# electrophy_NRF.net
KiCad netlist of a schematic drawn in EAGLE
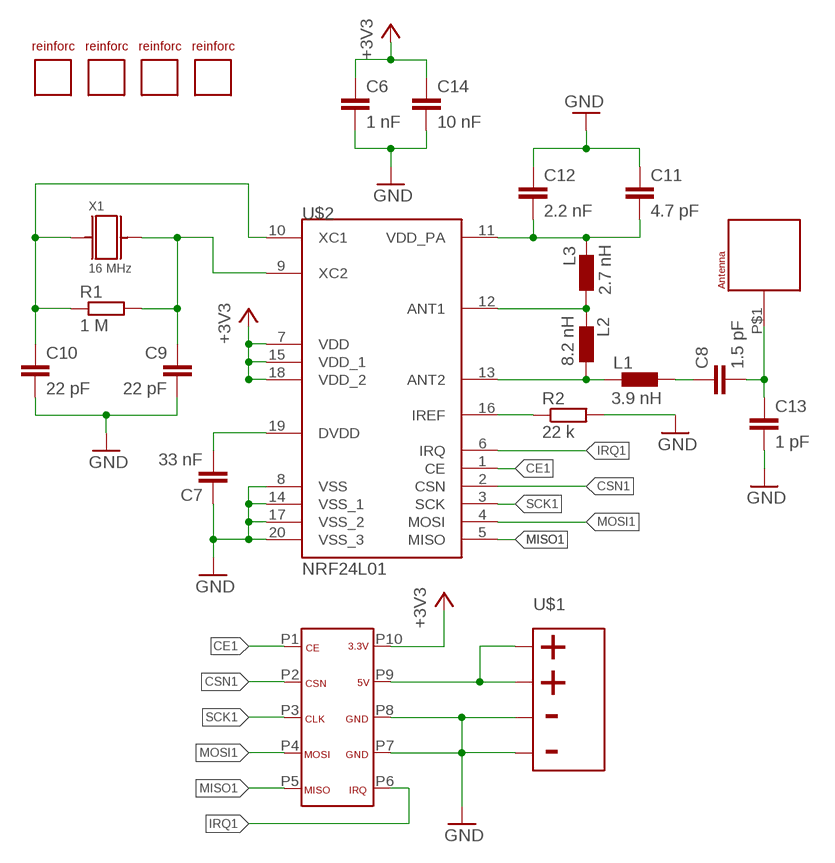
[diagram p0: schematic, sheet 1]

(export (version "E")
  (design (tool "Eeschema 10.0.6"))
  (components
    (comp (ref "C6")
      (value "1 nF")
      (footprint "eagle-import:C0603")
      (libsource (lib "eagle-import") (part "C-EUC0603"))
    )
    (comp (ref "C7")
      (value "33 nF")
      (footprint "eagle-import:C0603")
      (libsource (lib "eagle-import") (part "C-EUC0603"))
    )
    (comp (ref "C8")
      (value "1.5 pF")
      (footprint "eagle-import:C0603")
      (libsource (lib "eagle-import") (part "C-EUC0603"))
    )
    (comp (ref "C9")
      (value "22 pF")
      (footprint "eagle-import:C0603")
      (libsource (lib "eagle-import") (part "C-EUC0603"))
    )
    (comp (ref "C10")
      (value "22 pF")
      (footprint "eagle-import:C0603")
      (libsource (lib "eagle-import") (part "C-EUC0603"))
    )
    (comp (ref "C11")
      (value "4.7 pF")
      (footprint "eagle-import:C0603")
      (libsource (lib "eagle-import") (part "C-EUC0603"))
    )
    (comp (ref "C12")
      (value "2.2 nF")
      (footprint "eagle-import:C0603")
      (libsource (lib "eagle-import") (part "C-EUC0603"))
    )
    (comp (ref "C13")
      (value "1 pF")
      (footprint "eagle-import:C0603")
      (libsource (lib "eagle-import") (part "C-EUC0603"))
    )
    (comp (ref "C14")
      (value "10 nF")
      (footprint "eagle-import:C0603")
      (libsource (lib "eagle-import") (part "C-EUC0603"))
    )
    (comp (ref "L1")
      (value "3.9 nH")
      (footprint "eagle-import:C0603")
      (libsource (lib "eagle-import") (part "INDUCTANCE"))
    )
    (comp (ref "L2")
      (value "8.2 nH")
      (footprint "eagle-import:C0603")
      (libsource (lib "eagle-import") (part "INDUCTANCE"))
    )
    (comp (ref "L3")
      (value "2.7 nH")
      (footprint "eagle-import:C0603")
      (libsource (lib "eagle-import") (part "INDUCTANCE"))
    )
    (comp (ref "R1")
      (value "1 M")
      (footprint "eagle-import:R0603")
      (libsource (lib "eagle-import") (part "R-EU_R0603"))
    )
    (comp (ref "R2")
      (value "22 k")
      (footprint "eagle-import:R0603")
      (libsource (lib "eagle-import") (part "R-EU_R0603"))
    )
    (comp (ref "U$1")
      (value "BAT_HOLDER")
      (footprint "eagle-import:BAT_HOLDER")
      (libsource (lib "eagle-import") (part "BAT_HOLDER"))
    )
    (comp (ref "U$2")
      (value "NRF24L01")
      (footprint "eagle-import:QFN20")
      (libsource (lib "eagle-import") (part "NRF24L01"))
    )
    (comp (ref "U$3")
      (value "WURTH_ANTENNA")
      (footprint "eagle-import:WURTH_ANTENNA")
      (libsource (lib "eagle-import") (part "WURTH_ANTENNA"))
    )
    (comp (ref "U$4")
      (value "DF12-10-MALE")
      (footprint "eagle-import:DF12-10-MALE")
      (libsource (lib "eagle-import") (part "DF12-10-MALE"))
    )
    (comp (ref "U$5")
      (value "REINFORCEMENT")
      (footprint "eagle-import:REINFORCEMENT")
      (libsource (lib "eagle-import") (part "REINFORCEMENT"))
    )
    (comp (ref "U$6")
      (value "REINFORCEMENT")
      (footprint "eagle-import:REINFORCEMENT")
      (libsource (lib "eagle-import") (part "REINFORCEMENT"))
    )
    (comp (ref "U$7")
      (value "REINFORCEMENT")
      (footprint "eagle-import:REINFORCEMENT")
      (libsource (lib "eagle-import") (part "REINFORCEMENT"))
    )
    (comp (ref "U$8")
      (value "REINFORCEMENT")
      (footprint "eagle-import:REINFORCEMENT")
      (libsource (lib "eagle-import") (part "REINFORCEMENT"))
    )
    (comp (ref "X1")
      (value "16 MHz")
      (footprint "eagle-import:NRF_XTAL")
      (libsource (lib "eagle-import") (part "NRF_XTAL"))
    )
  )
  (nets
    (net (code "1") (name "+3V3") (class "Default")
      (node (ref "C14") (pin "1") (pinfunction "1_1") (pintype "passive"))
      (node (ref "C6") (pin "1") (pinfunction "1_1") (pintype "passive"))
      (node (ref "U$2") (pin "15") (pinfunction "VDD_1_15") (pintype "bidirectional"))
      (node (ref "U$2") (pin "18") (pinfunction "VDD_2_18") (pintype "bidirectional"))
      (node (ref "U$2") (pin "7") (pinfunction "VDD_7") (pintype "bidirectional"))
      (node (ref "U$4") (pin "P10") (pinfunction "P10_P10") (pintype "passive"))
    )
    (net (code "2") (name "CE1") (class "Default")
      (node (ref "U$2") (pin "1") (pinfunction "CE_1") (pintype "bidirectional"))
      (node (ref "U$4") (pin "P1") (pinfunction "P1_P1") (pintype "passive"))
    )
    (net (code "3") (name "CSN1") (class "Default")
      (node (ref "U$2") (pin "2") (pinfunction "CSN_2") (pintype "bidirectional"))
      (node (ref "U$4") (pin "P2") (pinfunction "P2_P2") (pintype "passive"))
    )
    (net (code "4") (name "GND") (class "Default")
      (node (ref "C10") (pin "2") (pinfunction "2_2") (pintype "passive"))
      (node (ref "C11") (pin "1") (pinfunction "1_1") (pintype "passive"))
      (node (ref "C12") (pin "1") (pinfunction "1_1") (pintype "passive"))
      (node (ref "C13") (pin "2") (pinfunction "2_2") (pintype "passive"))
      (node (ref "C14") (pin "2") (pinfunction "2_2") (pintype "passive"))
      (node (ref "C6") (pin "2") (pinfunction "2_2") (pintype "passive"))
      (node (ref "C7") (pin "1") (pinfunction "1_1") (pintype "passive"))
      (node (ref "C9") (pin "2") (pinfunction "2_2") (pintype "passive"))
      (node (ref "R2") (pin "2") (pinfunction "2_2") (pintype "passive"))
      (node (ref "U$1") (pin "PMOINS") (pinfunction "PMOINS_PMOINS") (pintype "power_in"))
      (node (ref "U$1") (pin "PMOINSBIS") (pinfunction "PMOINSBIS_PMOINSBIS") (pintype "power_in"))
      (node (ref "U$2") (pin "14") (pinfunction "VSS_1_14") (pintype "bidirectional"))
      (node (ref "U$2") (pin "17") (pinfunction "VSS_2_17") (pintype "bidirectional"))
      (node (ref "U$2") (pin "20") (pinfunction "VSS_3_20") (pintype "bidirectional"))
      (node (ref "U$2") (pin "8") (pinfunction "VSS_8") (pintype "bidirectional"))
      (node (ref "U$4") (pin "P7") (pinfunction "P7_P7") (pintype "passive"))
      (node (ref "U$4") (pin "P8") (pinfunction "P8_P8") (pintype "passive"))
    )
    (net (code "5") (name "IRQ1") (class "Default")
      (node (ref "U$2") (pin "6") (pinfunction "IRQ_6") (pintype "bidirectional"))
      (node (ref "U$4") (pin "P6") (pinfunction "P6_P6") (pintype "passive"))
    )
    (net (code "6") (name "MISO1") (class "Default")
      (node (ref "U$2") (pin "5") (pinfunction "MISO_5") (pintype "bidirectional"))
      (node (ref "U$4") (pin "P5") (pinfunction "P5_P5") (pintype "passive"))
    )
    (net (code "7") (name "MOSI1") (class "Default")
      (node (ref "U$2") (pin "4") (pinfunction "MOSI_4") (pintype "bidirectional"))
      (node (ref "U$4") (pin "P4") (pinfunction "P4_P4") (pintype "passive"))
    )
    (net (code "8") (name "Net-(C8-Pad1)") (class "Default")
      (node (ref "C8") (pin "1") (pinfunction "1_1") (pintype "passive"))
      (node (ref "L1") (pin "1") (pinfunction "1_1") (pintype "passive"))
    )
    (net (code "9") (name "Net-(C13-Pad1)") (class "Default")
      (node (ref "C13") (pin "1") (pinfunction "1_1") (pintype "passive"))
      (node (ref "C8") (pin "2") (pinfunction "2_2") (pintype "passive"))
      (node (ref "U$3") (pin "P$1") (pinfunction "P$1_P$1") (pintype "passive"))
    )
    (net (code "10") (name "Net-(U$1-PadPPLUS)") (class "Default")
      (node (ref "U$1") (pin "PPLUS") (pinfunction "PPLUS_PPLUS") (pintype "power_in"))
      (node (ref "U$1") (pin "PPLUSBIS") (pinfunction "PPLUSBIS_PPLUSBIS") (pintype "power_in"))
      (node (ref "U$4") (pin "P9") (pinfunction "P9_P9") (pintype "passive"))
    )
    (net (code "11") (name "Net-(U$2-ANT1)") (class "Default")
      (node (ref "L2") (pin "2") (pinfunction "2_2") (pintype "passive"))
      (node (ref "L3") (pin "1") (pinfunction "1_1") (pintype "passive"))
      (node (ref "U$2") (pin "12") (pinfunction "ANT1_12") (pintype "bidirectional"))
    )
    (net (code "12") (name "Net-(U$2-ANT2)") (class "Default")
      (node (ref "L1") (pin "2") (pinfunction "2_2") (pintype "passive"))
      (node (ref "L2") (pin "1") (pinfunction "1_1") (pintype "passive"))
      (node (ref "U$2") (pin "13") (pinfunction "ANT2_13") (pintype "bidirectional"))
    )
    (net (code "13") (name "Net-(U$2-DVDD)") (class "Default")
      (node (ref "C7") (pin "2") (pinfunction "2_2") (pintype "passive"))
      (node (ref "U$2") (pin "19") (pinfunction "DVDD_19") (pintype "bidirectional"))
    )
    (net (code "14") (name "Net-(U$2-IREF)") (class "Default")
      (node (ref "R2") (pin "1") (pinfunction "1_1") (pintype "passive"))
      (node (ref "U$2") (pin "16") (pinfunction "IREF_16") (pintype "bidirectional"))
    )
    (net (code "15") (name "Net-(U$2-VDD_PA)") (class "Default")
      (node (ref "C11") (pin "2") (pinfunction "2_2") (pintype "passive"))
      (node (ref "C12") (pin "2") (pinfunction "2_2") (pintype "passive"))
      (node (ref "L3") (pin "2") (pinfunction "2_2") (pintype "passive"))
      (node (ref "U$2") (pin "11") (pinfunction "VDD_PA_11") (pintype "bidirectional"))
    )
    (net (code "16") (name "Net-(U$2-XC1)") (class "Default")
      (node (ref "C10") (pin "1") (pinfunction "1_1") (pintype "passive"))
      (node (ref "R1") (pin "1") (pinfunction "1_1") (pintype "passive"))
      (node (ref "U$2") (pin "10") (pinfunction "XC1_10") (pintype "bidirectional"))
      (node (ref "X1") (pin "P$2") (pinfunction "2_P$2") (pintype "passive"))
    )
    (net (code "17") (name "Net-(U$2-XC2)") (class "Default")
      (node (ref "C9") (pin "1") (pinfunction "1_1") (pintype "passive"))
      (node (ref "R1") (pin "2") (pinfunction "2_2") (pintype "passive"))
      (node (ref "U$2") (pin "9") (pinfunction "XC2_9") (pintype "bidirectional"))
      (node (ref "X1") (pin "P$1") (pinfunction "1_P$1") (pintype "passive"))
    )
    (net (code "18") (name "SCK1") (class "Default")
      (node (ref "U$2") (pin "3") (pinfunction "SCK_3") (pintype "bidirectional"))
      (node (ref "U$4") (pin "P3") (pinfunction "P3_P3") (pintype "passive"))
    )
    (net (code "19") (name "unconnected-(U$5-PadP$1)") (class "Default")
      (node (ref "U$5") (pin "P$1") (pinfunction "P$1_P$1") (pintype "bidirectional"))
    )
    (net (code "20") (name "unconnected-(U$6-PadP$1)") (class "Default")
      (node (ref "U$6") (pin "P$1") (pinfunction "P$1_P$1") (pintype "bidirectional"))
    )
    (net (code "21") (name "unconnected-(U$7-PadP$1)") (class "Default")
      (node (ref "U$7") (pin "P$1") (pinfunction "P$1_P$1") (pintype "bidirectional"))
    )
    (net (code "22") (name "unconnected-(U$8-PadP$1)") (class "Default")
      (node (ref "U$8") (pin "P$1") (pinfunction "P$1_P$1") (pintype "bidirectional"))
    )
  )
)
